# mood_ring.net
KiCad netlist of a schematic drawn in EAGLE
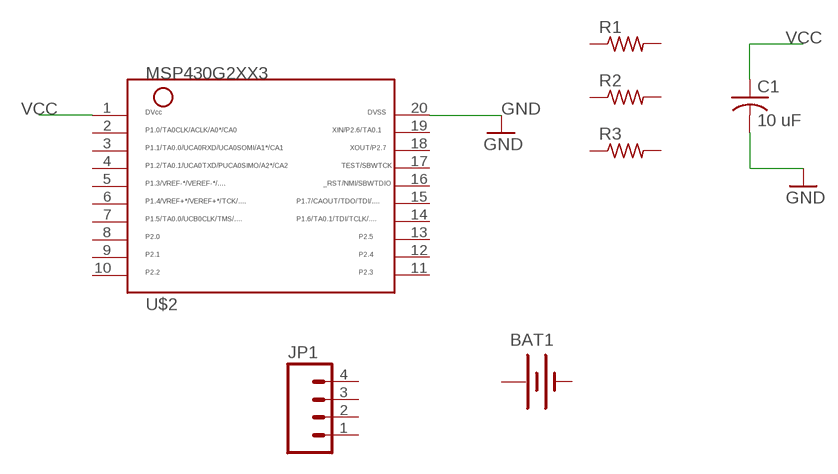
[diagram p0: schematic, sheet 1]

(export (version "E")
  (design (tool "Eeschema 10.0.6"))
  (components
    (comp (ref "BAT1")
      (value "BATTERYBU2032SM")
      (footprint "eagle-import:BU2032SM")
      (libsource (lib "eagle-import") (part "BATTERYBU2032SM"))
    )
    (comp (ref "C1")
      (value "10 uF")
      (footprint "eagle-import:C1206")
      (libsource (lib "eagle-import") (part "C-USC1206"))
    )
    (comp (ref "JP1")
      (value "M04LOCK")
      (footprint "eagle-import:1X04_LOCK")
      (libsource (lib "eagle-import") (part "M04LOCK"))
    )
    (comp (ref "R1")
      (value "R-US_R1206")
      (footprint "eagle-import:R1206")
      (libsource (lib "eagle-import") (part "R-US_R1206"))
    )
    (comp (ref "R2")
      (value "R-US_R1206")
      (footprint "eagle-import:R1206")
      (libsource (lib "eagle-import") (part "R-US_R1206"))
    )
    (comp (ref "R3")
      (value "R-US_R1206")
      (footprint "eagle-import:R1206")
      (libsource (lib "eagle-import") (part "R-US_R1206"))
    )
    (comp (ref "U$2")
      (value "MSP430G2XX3TSSOP")
      (footprint "eagle-import:PW20")
      (libsource (lib "eagle-import") (part "MSP430G2XX3TSSOP"))
    )
  )
  (nets
    (net (code "1") (name "/+") (class "Default")
      (node (ref "BAT1") (pin "P$1") (pinfunction "+_P$1") (pintype "power_in"))
    )
    (net (code "2") (name "/-") (class "Default")
      (node (ref "BAT1") (pin "P$2") (pinfunction "-_P$2") (pintype "power_in"))
    )
    (net (code "3") (name "/VCC") (class "Default")
      (node (ref "C1") (pin "1") (pinfunction "1_1") (pintype "passive"))
      (node (ref "U$2") (pin "1") (pinfunction "1_1") (pintype "bidirectional"))
    )
    (net (code "4") (name "GND") (class "Default")
      (node (ref "C1") (pin "2") (pinfunction "2_2") (pintype "passive"))
      (node (ref "U$2") (pin "20") (pinfunction "20_20") (pintype "bidirectional"))
    )
    (net (code "5") (name "unconnected-(JP1-Pad1)") (class "Default")
      (node (ref "JP1") (pin "1") (pinfunction "1_1") (pintype "passive"))
    )
    (net (code "6") (name "unconnected-(JP1-Pad2)") (class "Default")
      (node (ref "JP1") (pin "2") (pinfunction "2_2") (pintype "passive"))
    )
    (net (code "7") (name "unconnected-(JP1-Pad3)") (class "Default")
      (node (ref "JP1") (pin "3") (pinfunction "3_3") (pintype "passive"))
    )
    (net (code "8") (name "unconnected-(JP1-Pad4)") (class "Default")
      (node (ref "JP1") (pin "4") (pinfunction "4_4") (pintype "passive"))
    )
    (net (code "9") (name "unconnected-(R1-Pad1)") (class "Default")
      (node (ref "R1") (pin "1") (pinfunction "1_1") (pintype "passive"))
    )
    (net (code "10") (name "unconnected-(R1-Pad2)") (class "Default")
      (node (ref "R1") (pin "2") (pinfunction "2_2") (pintype "passive"))
    )
    (net (code "11") (name "unconnected-(R2-Pad1)") (class "Default")
      (node (ref "R2") (pin "1") (pinfunction "1_1") (pintype "passive"))
    )
    (net (code "12") (name "unconnected-(R2-Pad2)") (class "Default")
      (node (ref "R2") (pin "2") (pinfunction "2_2") (pintype "passive"))
    )
    (net (code "13") (name "unconnected-(R3-Pad1)") (class "Default")
      (node (ref "R3") (pin "1") (pinfunction "1_1") (pintype "passive"))
    )
    (net (code "14") (name "unconnected-(R3-Pad2)") (class "Default")
      (node (ref "R3") (pin "2") (pinfunction "2_2") (pintype "passive"))
    )
    (net (code "15") (name "unconnected-(U$2-Pad2)") (class "Default")
      (node (ref "U$2") (pin "2") (pinfunction "2_2") (pintype "bidirectional"))
    )
    (net (code "16") (name "unconnected-(U$2-Pad3)") (class "Default")
      (node (ref "U$2") (pin "3") (pinfunction "3_3") (pintype "bidirectional"))
    )
    (net (code "17") (name "unconnected-(U$2-Pad4)") (class "Default")
      (node (ref "U$2") (pin "4") (pinfunction "4_4") (pintype "bidirectional"))
    )
    (net (code "18") (name "unconnected-(U$2-Pad5)") (class "Default")
      (node (ref "U$2") (pin "5") (pinfunction "5_5") (pintype "bidirectional"))
    )
    (net (code "19") (name "unconnected-(U$2-Pad6)") (class "Default")
      (node (ref "U$2") (pin "6") (pinfunction "6_6") (pintype "bidirectional"))
    )
    (net (code "20") (name "unconnected-(U$2-Pad7)") (class "Default")
      (node (ref "U$2") (pin "7") (pinfunction "7_7") (pintype "bidirectional"))
    )
    (net (code "21") (name "unconnected-(U$2-Pad8)") (class "Default")
      (node (ref "U$2") (pin "8") (pinfunction "8_8") (pintype "bidirectional"))
    )
    (net (code "22") (name "unconnected-(U$2-Pad9)") (class "Default")
      (node (ref "U$2") (pin "9") (pinfunction "9_9") (pintype "bidirectional"))
    )
    (net (code "23") (name "unconnected-(U$2-Pad10)") (class "Default")
      (node (ref "U$2") (pin "10") (pinfunction "10_10") (pintype "bidirectional"))
    )
    (net (code "24") (name "unconnected-(U$2-Pad11)") (class "Default")
      (node (ref "U$2") (pin "11") (pinfunction "11_11") (pintype "bidirectional"))
    )
    (net (code "25") (name "unconnected-(U$2-Pad12)") (class "Default")
      (node (ref "U$2") (pin "12") (pinfunction "12_12") (pintype "bidirectional"))
    )
    (net (code "26") (name "unconnected-(U$2-Pad13)") (class "Default")
      (node (ref "U$2") (pin "13") (pinfunction "13_13") (pintype "bidirectional"))
    )
    (net (code "27") (name "unconnected-(U$2-Pad14)") (class "Default")
      (node (ref "U$2") (pin "14") (pinfunction "14_14") (pintype "bidirectional"))
    )
    (net (code "28") (name "unconnected-(U$2-Pad15)") (class "Default")
      (node (ref "U$2") (pin "15") (pinfunction "15_15") (pintype "bidirectional"))
    )
    (net (code "29") (name "unconnected-(U$2-Pad16)") (class "Default")
      (node (ref "U$2") (pin "16") (pinfunction "16_16") (pintype "bidirectional"))
    )
    (net (code "30") (name "unconnected-(U$2-Pad17)") (class "Default")
      (node (ref "U$2") (pin "17") (pinfunction "17_17") (pintype "bidirectional"))
    )
    (net (code "31") (name "unconnected-(U$2-Pad18)") (class "Default")
      (node (ref "U$2") (pin "18") (pinfunction "18_18") (pintype "bidirectional"))
    )
    (net (code "32") (name "unconnected-(U$2-Pad19)") (class "Default")
      (node (ref "U$2") (pin "19") (pinfunction "19_19") (pintype "bidirectional"))
    )
  )
)
